# tritiled_v30_lux_c_reverse.net
KiCad netlist of a schematic drawn in EAGLE
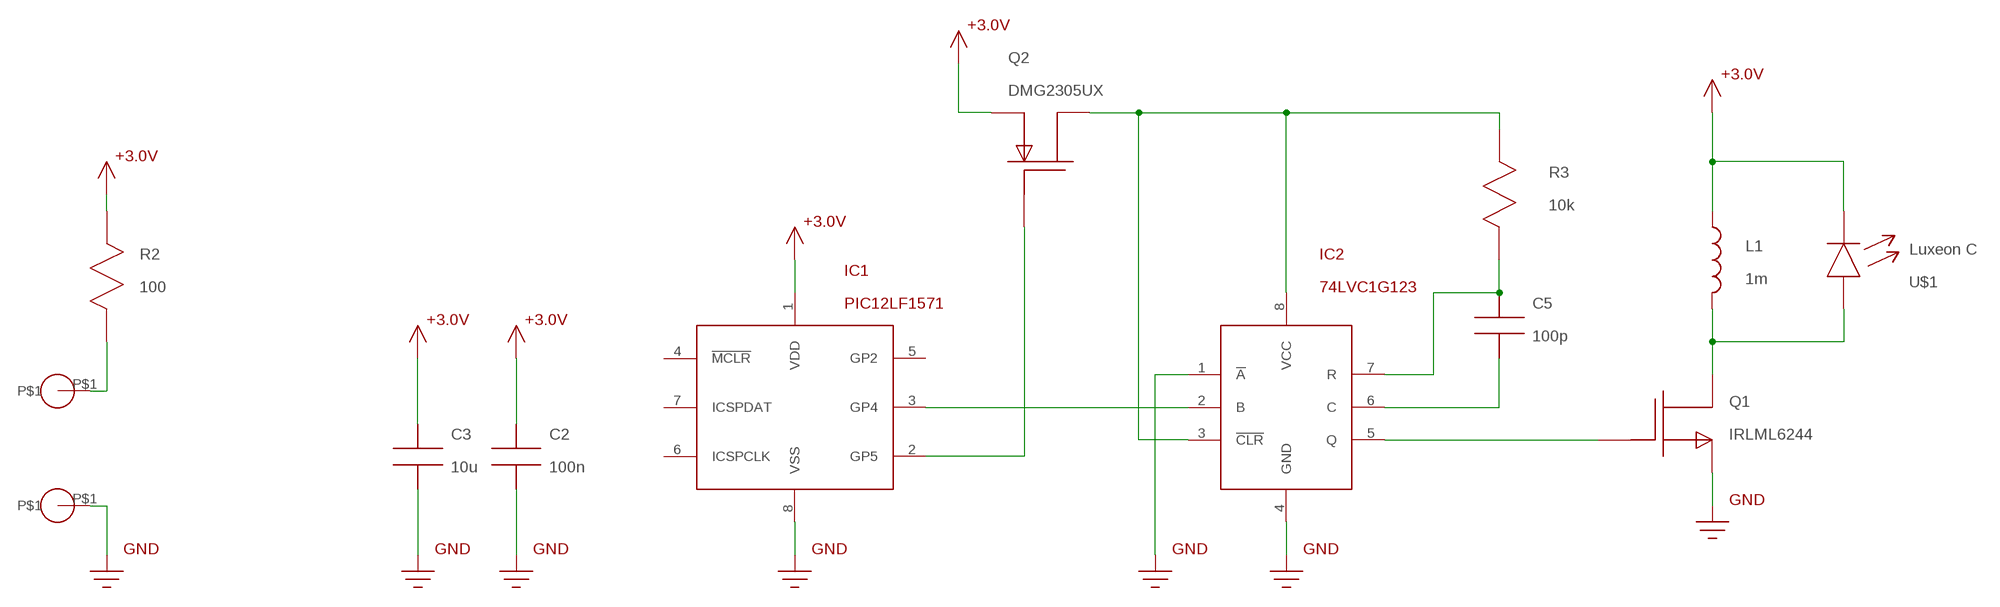
[diagram p0: schematic, sheet 1]

(export (version "E")
  (design (tool "Eeschema 10.0.6"))
  (components
    (comp (ref "C2")
      (value "100n")
      (footprint "eagle-import:0805")
      (libsource (lib "eagle-import") (part "C0805"))
    )
    (comp (ref "C3")
      (value "10u")
      (footprint "eagle-import:1206")
      (libsource (lib "eagle-import") (part "C1206"))
    )
    (comp (ref "C5")
      (value "100p")
      (footprint "eagle-import:C0603")
      (libsource (lib "eagle-import") (part "C0603"))
    )
    (comp (ref "IC1")
      (value "PIC12LF1571")
      (footprint "eagle-import:SOIC8")
      (libsource (lib "eagle-import") (part "PIC12LF1571"))
    )
    (comp (ref "IC2")
      (value "74LVC1G123")
      (footprint "eagle-import:SM8")
      (libsource (lib "eagle-import") (part "74LVC1G123"))
    )
    (comp (ref "L1")
      (value "1m")
      (footprint "eagle-import:SRR6028_INDUCTOR")
      (libsource (lib "eagle-import") (part "SRR6028_INDUCTOR"))
    )
    (comp (ref "Q1")
      (value "IRLML6244")
      (footprint "eagle-import:SOT-23")
      (libsource (lib "eagle-import") (part "ZXMN3B01FSOT23"))
    )
    (comp (ref "Q2")
      (value "DMG2305UX")
      (footprint "eagle-import:SOT-23")
      (libsource (lib "eagle-import") (part "DMG2305UXSOT23"))
    )
    (comp (ref "R2")
      (value "100")
      (footprint "eagle-import:R1206")
      (libsource (lib "eagle-import") (part "R1206"))
    )
    (comp (ref "R3")
      (value "10k")
      (footprint "eagle-import:R0603")
      (libsource (lib "eagle-import") (part "R0603"))
    )
    (comp (ref "U$1")
      (value "Luxeon C")
      (footprint "eagle-import:LUXEON_C")
      (libsource (lib "eagle-import") (part "LEDLUXEON_C"))
    )
    (comp (ref "U$2")
      (value "HDR_1_PIN")
      (footprint "eagle-import:HDR_1_PIN")
      (libsource (lib "eagle-import") (part "HDR_1_PIN"))
    )
    (comp (ref "U$5")
      (value "HDR_1_PIN")
      (footprint "eagle-import:HDR_1_PIN")
      (libsource (lib "eagle-import") (part "HDR_1_PIN"))
    )
  )
  (nets
    (net (code "1") (name "+3.0V") (class "Default")
      (node (ref "C2") (pin "P$1") (pinfunction "P$1_P$1") (pintype "bidirectional"))
      (node (ref "C3") (pin "P$1") (pinfunction "P$1_P$1") (pintype "bidirectional"))
      (node (ref "IC1") (pin "1") (pinfunction "VDD_1") (pintype "bidirectional"))
      (node (ref "L1") (pin "P$1") (pinfunction "1_P$1") (pintype "passive"))
      (node (ref "Q2") (pin "2") (pinfunction "S_2") (pintype "bidirectional"))
      (node (ref "R2") (pin "P$1") (pinfunction "P$1_P$1") (pintype "bidirectional"))
      (node (ref "U$1") (pin "C") (pinfunction "C_C") (pintype "bidirectional"))
    )
    (net (code "2") (name "GND") (class "Default")
      (node (ref "C2") (pin "P$2") (pinfunction "P$2_P$2") (pintype "bidirectional"))
      (node (ref "C3") (pin "P$2") (pinfunction "P$2_P$2") (pintype "bidirectional"))
      (node (ref "IC1") (pin "8") (pinfunction "VSS_8") (pintype "bidirectional"))
      (node (ref "IC2") (pin "1") (pinfunction "~{A}_1") (pintype "bidirectional"))
      (node (ref "IC2") (pin "4") (pinfunction "GND_4") (pintype "bidirectional"))
      (node (ref "Q1") (pin "2") (pinfunction "S_2") (pintype "bidirectional"))
      (node (ref "U$5") (pin "P$1") (pinfunction "P$1_P$1") (pintype "bidirectional"))
    )
    (net (code "3") (name "Net-(IC1-GP4)") (class "Default")
      (node (ref "IC1") (pin "3") (pinfunction "GP4_3") (pintype "bidirectional"))
      (node (ref "IC2") (pin "2") (pinfunction "B_2") (pintype "bidirectional"))
    )
    (net (code "4") (name "Net-(IC1-GP5)") (class "Default")
      (node (ref "IC1") (pin "2") (pinfunction "GP5_2") (pintype "bidirectional"))
      (node (ref "Q2") (pin "1") (pinfunction "G_1") (pintype "bidirectional"))
    )
    (net (code "5") (name "Net-(IC2-C)") (class "Default")
      (node (ref "C5") (pin "P$2") (pinfunction "P$2_P$2") (pintype "bidirectional"))
      (node (ref "IC2") (pin "6") (pinfunction "C_6") (pintype "bidirectional"))
    )
    (net (code "6") (name "Net-(IC2-Q)") (class "Default")
      (node (ref "IC2") (pin "5") (pinfunction "Q_5") (pintype "bidirectional"))
      (node (ref "Q1") (pin "1") (pinfunction "G_1") (pintype "bidirectional"))
    )
    (net (code "7") (name "Net-(IC2-R)") (class "Default")
      (node (ref "C5") (pin "P$1") (pinfunction "P$1_P$1") (pintype "bidirectional"))
      (node (ref "IC2") (pin "7") (pinfunction "R_7") (pintype "bidirectional"))
      (node (ref "R3") (pin "P$1") (pinfunction "P$1_P$1") (pintype "bidirectional"))
    )
    (net (code "8") (name "Net-(IC2-VCC)") (class "Default")
      (node (ref "IC2") (pin "3") (pinfunction "~{CLR}_3") (pintype "bidirectional"))
      (node (ref "IC2") (pin "8") (pinfunction "VCC_8") (pintype "bidirectional"))
      (node (ref "Q2") (pin "3") (pinfunction "D_3") (pintype "bidirectional"))
      (node (ref "R3") (pin "P$2") (pinfunction "P$2_P$2") (pintype "bidirectional"))
    )
    (net (code "9") (name "Net-(L1-2)") (class "Default")
      (node (ref "L1") (pin "P$2") (pinfunction "2_P$2") (pintype "passive"))
      (node (ref "Q1") (pin "3") (pinfunction "D_3") (pintype "bidirectional"))
      (node (ref "U$1") (pin "A") (pinfunction "A_A") (pintype "bidirectional"))
    )
    (net (code "10") (name "Net-(R2-PadP$2)") (class "Default")
      (node (ref "R2") (pin "P$2") (pinfunction "P$2_P$2") (pintype "bidirectional"))
      (node (ref "U$2") (pin "P$1") (pinfunction "P$1_P$1") (pintype "bidirectional"))
    )
    (net (code "11") (name "unconnected-(IC1-GP2-Pad5)") (class "Default")
      (node (ref "IC1") (pin "5") (pinfunction "GP2_5") (pintype "bidirectional"))
    )
    (net (code "12") (name "unconnected-(IC1-ICSPCLK-Pad6)") (class "Default")
      (node (ref "IC1") (pin "6") (pinfunction "ICSPCLK_6") (pintype "bidirectional"))
    )
    (net (code "13") (name "unconnected-(IC1-ICSPDAT-Pad7)") (class "Default")
      (node (ref "IC1") (pin "7") (pinfunction "ICSPDAT_7") (pintype "bidirectional"))
    )
    (net (code "14") (name "unconnected-(IC1-~{MCLR}-Pad4)") (class "Default")
      (node (ref "IC1") (pin "4") (pinfunction "~{MCLR}_4") (pintype "bidirectional"))
    )
  )
)
